# MagnetSensor.net
KiCad netlist of a schematic drawn in Altium Designer
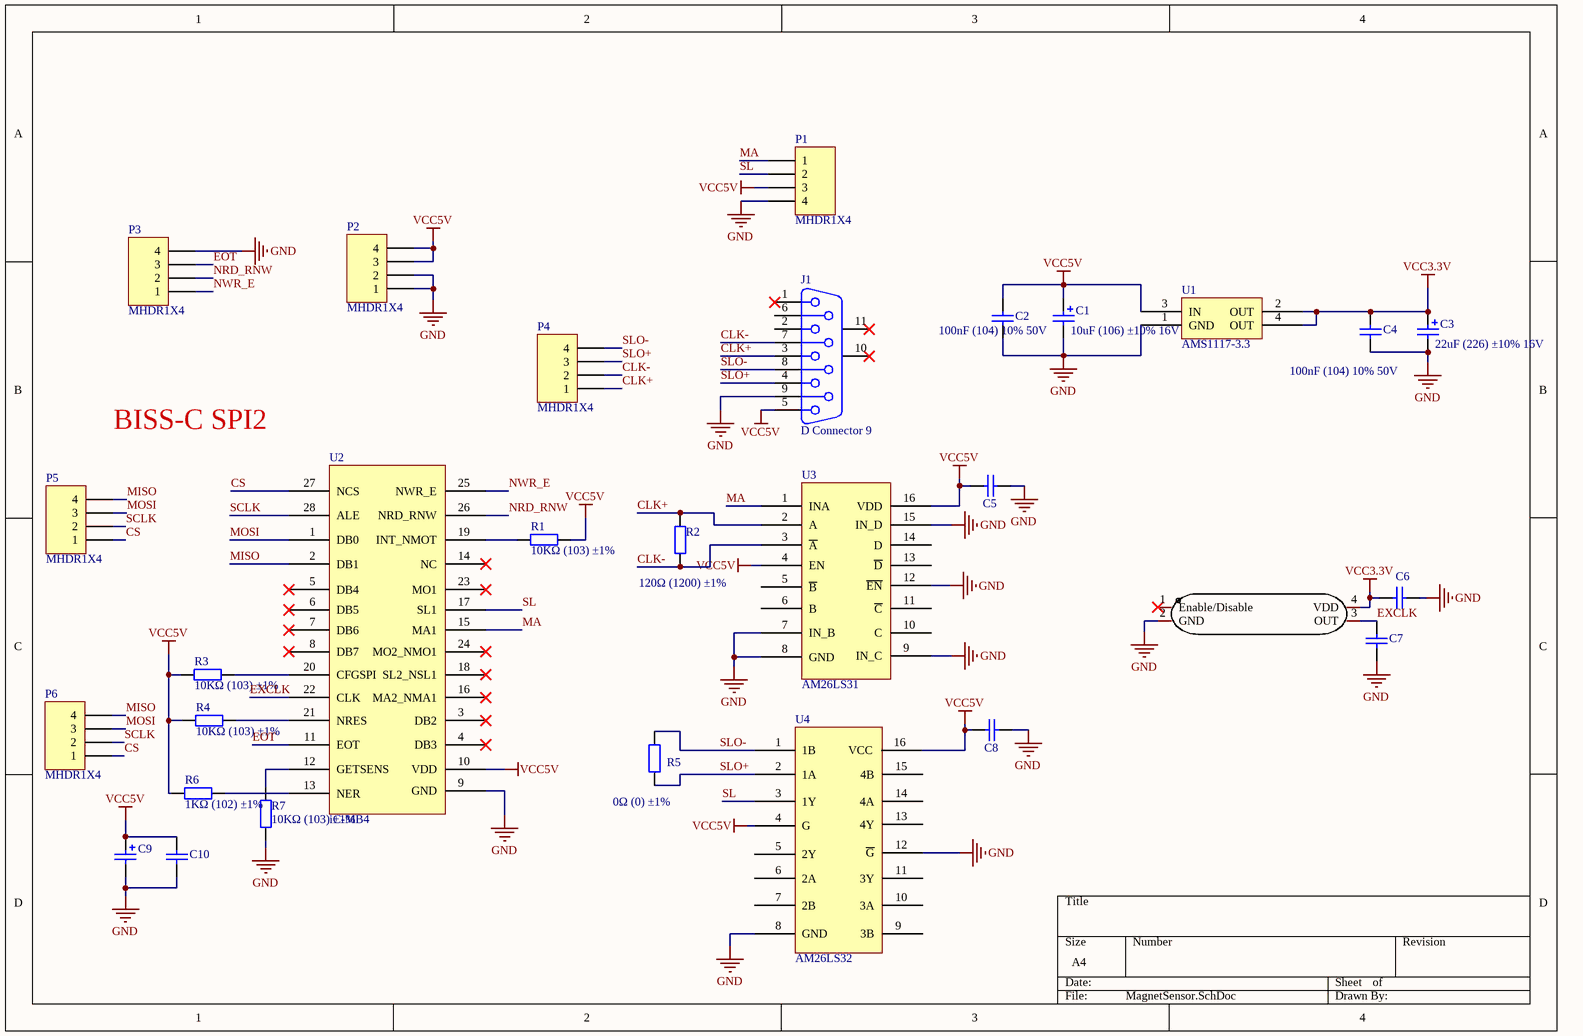
[diagram p0: MagnetSensor.SchDoc]

(export (version "E")
  (design (tool "Eeschema 10.0.6"))
  (components
    (comp (ref "C1")
      (value "10uF (106) ±10% 16V")
      (footprint "CASE-A_3216")
      (description "钽电容")
      (libsource (lib "Cap") (part "3216 10uF (106) 10% 16V"))
    )
    (comp (ref "C2")
      (value "100nF (104) 10% 50V")
      (footprint "0603_C")
      (description "贴片电容")
      (libsource (lib "Cap") (part "0603 100nF (104) 10% 50V"))
    )
    (comp (ref "C3")
      (value "22uF (226) ±10% 16V")
      (footprint "CASE-B_3528")
      (description "钽电容")
      (libsource (lib "Cap") (part "3216 10uF (106) 10% 16V"))
    )
    (comp (ref "C4")
      (value "100nF (104) 10% 50V")
      (footprint "0603_C")
      (description "贴片电容")
      (libsource (lib "Cap") (part "0603 100nF (104) 10% 50V"))
    )
    (comp (ref "C5")
      (value "100nF (104) 10% 50V")
      (footprint "0603_C")
      (description "贴片电容")
      (libsource (lib "Miscellaneous Devices LC") (part "0603 100nF (104) 10% 50V"))
    )
    (comp (ref "C6")
      (value "100nF (104) 10% 50V")
      (footprint "0603_C")
      (description "贴片电容")
      (libsource (lib "Miscellaneous Devices LC") (part "0603 100nF (104) 10% 50V"))
    )
    (comp (ref "C7")
      (value "15uF (104) 10% 50V")
      (footprint "0805_C")
      (description "贴片电容")
      (libsource (lib "Miscellaneous Devices LC") (part "0603 100nF (104) 10% 50V"))
    )
    (comp (ref "C8")
      (value "100nF (104) 10% 50V")
      (footprint "0603_C")
      (description "贴片电容")
      (libsource (lib "Miscellaneous Devices LC") (part "0603 100nF (104) 10% 50V"))
    )
    (comp (ref "C9")
      (value "10uF (106) ±10% 16V")
      (footprint "CASE-A_3216")
      (description "钽电容")
      (libsource (lib "Miscellaneous Devices LC") (part "3216 10uF (106) 10% 16V"))
    )
    (comp (ref "C10")
      (value "100nF (104) 10% 50V")
      (footprint "0603_C")
      (description "贴片电容")
      (libsource (lib "Miscellaneous Devices LC") (part "0603 100nF (104) 10% 50V"))
    )
    (comp (ref "J1")
      (value "D Connector 9")
      (footprint "DSUB1.385-2H9")
      (description "Receptacle Assembly, 9 Position, Right Angle")
      (fields (field (name "PUBLISHER") "Altium Limited"))
      (libsource (lib "Miscellaneous Connectors") (part "D Connector 9"))
    )
    (comp (ref "P1")
      (value "MHDR1X4")
      (footprint "SH1.0-4P-L")
      (description "Header, 4-Pin")
      (fields (field (name "PUBLISHER") "Altium Limited"))
      (libsource (lib "") (part "MHDR1X4_1"))
    )
    (comp (ref "P2")
      (value "MHDR1X4")
      (footprint "SH1.0-4P-L")
      (description "Header, 4-Pin")
      (fields (field (name "PUBLISHER") "Altium Limited"))
      (libsource (lib "Miscellaneous Connectors") (part "MHDR1X4"))
    )
    (comp (ref "P3")
      (value "MHDR1X4")
      (footprint "SH1.0-4P-L")
      (description "Header, 4-Pin")
      (fields (field (name "PUBLISHER") "Altium Limited"))
      (libsource (lib "Miscellaneous Connectors") (part "MHDR1X4"))
    )
    (comp (ref "P4")
      (value "MHDR1X4")
      (footprint "SH1.0-4P-L")
      (description "Header, 4-Pin")
      (fields (field (name "PUBLISHER") "Altium Limited"))
      (libsource (lib "Miscellaneous Connectors") (part "MHDR1X4"))
    )
    (comp (ref "P5")
      (value "MHDR1X4")
      (footprint "SH1.0-4P-L")
      (description "Header, 4-Pin")
      (fields (field (name "PUBLISHER") "Altium Limited"))
      (libsource (lib "Miscellaneous Connectors") (part "MHDR1X4"))
    )
    (comp (ref "P6")
      (value "MHDR1X4")
      (footprint "SH1.0-4P-L")
      (description "Header, 4-Pin")
      (fields (field (name "PUBLISHER") "Altium Limited"))
      (libsource (lib "Miscellaneous Connectors") (part "MHDR1X4"))
    )
    (comp (ref "R1")
      (value "10KΩ (103) ±1%")
      (footprint "0603_R")
      (description "贴片电阻")
      (libsource (lib "") (part "0603 360Ω (3600) 1%_1"))
    )
    (comp (ref "R2")
      (value "120Ω (1200) ±1%")
      (footprint "0603_R")
      (description "贴片电阻")
      (libsource (lib "RES") (part "0603 360Ω (3600) 1%"))
    )
    (comp (ref "R3")
      (value "10KΩ (103) ±1%")
      (footprint "0603_R")
      (description "贴片电阻")
      (libsource (lib "") (part "0603 360Ω (3600) 1%_1"))
    )
    (comp (ref "R4")
      (value "10KΩ (103) ±1%")
      (footprint "0603_R")
      (description "贴片电阻")
      (libsource (lib "") (part "0603 360Ω (3600) 1%_1"))
    )
    (comp (ref "R5")
      (value "0Ω (0) ±1%")
      (footprint "0603_R")
      (description "贴片电阻")
      (libsource (lib "RES") (part "0603 360Ω (3600) 1%"))
    )
    (comp (ref "R6")
      (value "1KΩ (102) ±1%")
      (footprint "0603_R")
      (description "贴片电阻")
      (libsource (lib "") (part "0603 360Ω (3600) 1%_2"))
    )
    (comp (ref "R7")
      (value "10KΩ (103) ±1%")
      (footprint "0603_R")
      (description "贴片电阻")
      (libsource (lib "RES") (part "0603 360Ω (3600) 1%"))
    )
    (comp (ref "U1")
      (value "AMS1117-3.3")
      (footprint "SOT-223")
      (description "3.3V稳压芯片")
      (libsource (lib "Library") (part "AMS1117"))
    )
    (comp (ref "U2")
      (value "iC-MB4")
      (footprint "QFN-28_5x5x05P")
      (description "SPI转BiSS主站芯片")
      (libsource (lib "CAS") (part "iC-MB4"))
    )
    (comp (ref "U3")
      (value "AM26LS31")
      (footprint "SO-16_N")
      (description "AM32LS31 单端转差分芯片")
      (libsource (lib "CAS") (part "AM26LS31"))
    )
    (comp (ref "U4")
      (value "AM26LS32")
      (footprint "SO-16_N")
      (description "AM26LS32 差分转单端")
      (libsource (lib "CAS") (part "AM26LS32"))
    )
    (comp (ref "X1")
      (value "20MHz")
      (footprint "OSC-SMD_4P-L2.5-W2.0-BL")
      (description "2015 osc")
      (fields (field (name "MANUFACTURER") "YXC(扬兴晶振)") (field (name "MANUFACTURER PART") "OT252020MJBA4SL"))
      (libsource (lib "altium-import") (part "root_0_OT252020MJBA4SL_"))
    )
  )
  (nets
    (net (code "1") (name "/CLK+") (class "Default")
      (node (ref "J1") (pin "3") (pinfunction "3_3") (pintype "passive"))
      (node (ref "P4") (pin "1") (pinfunction "1_1") (pintype "passive"))
      (node (ref "R2") (pin "1") (pinfunction "1_1") (pintype "passive"))
      (node (ref "U3") (pin "2") (pinfunction "A_2") (pintype "passive"))
    )
    (net (code "2") (name "/CLK-") (class "Default")
      (node (ref "J1") (pin "7") (pinfunction "7_7") (pintype "passive"))
      (node (ref "P4") (pin "2") (pinfunction "2_2") (pintype "passive"))
      (node (ref "R2") (pin "2") (pinfunction "2_2") (pintype "passive"))
      (node (ref "U3") (pin "3") (pinfunction "~{A}_3") (pintype "passive"))
    )
    (net (code "3") (name "/CS") (class "Default")
      (node (ref "P5") (pin "1") (pinfunction "1_1") (pintype "passive"))
      (node (ref "P6") (pin "1") (pinfunction "1_1") (pintype "passive"))
      (node (ref "U2") (pin "27") (pinfunction "NCS_27") (pintype "passive"))
    )
    (net (code "4") (name "/EOT") (class "Default")
      (node (ref "P3") (pin "3") (pinfunction "3_3") (pintype "passive"))
      (node (ref "U2") (pin "11") (pinfunction "EOT_11") (pintype "passive"))
    )
    (net (code "5") (name "/EXCLK") (class "Default")
      (node (ref "C7") (pin "2") (pinfunction "2_2") (pintype "passive"))
      (node (ref "U2") (pin "22") (pinfunction "CLK_22") (pintype "passive"))
      (node (ref "X1") (pin "3") (pinfunction "OUT_3") (pintype "passive"))
    )
    (net (code "6") (name "/MA") (class "Default")
      (node (ref "P1") (pin "1") (pinfunction "1_1") (pintype "passive"))
      (node (ref "U2") (pin "15") (pinfunction "MA1_15") (pintype "passive"))
      (node (ref "U3") (pin "1") (pinfunction "INA_1") (pintype "passive"))
    )
    (net (code "7") (name "/MISO") (class "Default")
      (node (ref "P5") (pin "4") (pinfunction "4_4") (pintype "passive"))
      (node (ref "P6") (pin "4") (pinfunction "4_4") (pintype "passive"))
      (node (ref "U2") (pin "2") (pinfunction "DB1_2") (pintype "passive"))
    )
    (net (code "8") (name "/MOSI") (class "Default")
      (node (ref "P5") (pin "3") (pinfunction "3_3") (pintype "passive"))
      (node (ref "P6") (pin "3") (pinfunction "3_3") (pintype "passive"))
      (node (ref "U2") (pin "1") (pinfunction "DB0_1") (pintype "passive"))
    )
    (net (code "9") (name "/NRD_RNW") (class "Default")
      (node (ref "P3") (pin "2") (pinfunction "2_2") (pintype "passive"))
      (node (ref "U2") (pin "26") (pinfunction "NRD_RNW_26") (pintype "passive"))
    )
    (net (code "10") (name "/NWR_E") (class "Default")
      (node (ref "P3") (pin "1") (pinfunction "1_1") (pintype "passive"))
      (node (ref "U2") (pin "25") (pinfunction "NWR_E_25") (pintype "passive"))
    )
    (net (code "11") (name "/SCLK") (class "Default")
      (node (ref "P5") (pin "2") (pinfunction "2_2") (pintype "passive"))
      (node (ref "P6") (pin "2") (pinfunction "2_2") (pintype "passive"))
      (node (ref "U2") (pin "28") (pinfunction "ALE_28") (pintype "passive"))
    )
    (net (code "12") (name "/SL") (class "Default")
      (node (ref "P1") (pin "2") (pinfunction "2_2") (pintype "passive"))
      (node (ref "U2") (pin "17") (pinfunction "SL1_17") (pintype "passive"))
      (node (ref "U4") (pin "3") (pinfunction "1Y_3") (pintype "passive"))
    )
    (net (code "13") (name "/SLO+") (class "Default")
      (node (ref "J1") (pin "4") (pinfunction "4_4") (pintype "passive"))
      (node (ref "P4") (pin "3") (pinfunction "3_3") (pintype "passive"))
      (node (ref "R5") (pin "2") (pinfunction "2_2") (pintype "passive"))
      (node (ref "U4") (pin "2") (pinfunction "1A_2") (pintype "passive"))
    )
    (net (code "14") (name "/SLO-") (class "Default")
      (node (ref "J1") (pin "8") (pinfunction "8_8") (pintype "passive"))
      (node (ref "P4") (pin "4") (pinfunction "4_4") (pintype "passive"))
      (node (ref "R5") (pin "1") (pinfunction "1_1") (pintype "passive"))
      (node (ref "U4") (pin "1") (pinfunction "1B_1") (pintype "passive"))
    )
    (net (code "15") (name "GND") (class "Default")
      (node (ref "C1") (pin "2") (pinfunction "2_2") (pintype "passive"))
      (node (ref "C10") (pin "1") (pinfunction "1_1") (pintype "passive"))
      (node (ref "C2") (pin "2") (pinfunction "2_2") (pintype "passive"))
      (node (ref "C3") (pin "2") (pinfunction "2_2") (pintype "passive"))
      (node (ref "C4") (pin "2") (pinfunction "2_2") (pintype "passive"))
      (node (ref "C5") (pin "1") (pinfunction "1_1") (pintype "passive"))
      (node (ref "C6") (pin "1") (pinfunction "1_1") (pintype "passive"))
      (node (ref "C7") (pin "1") (pinfunction "1_1") (pintype "passive"))
      (node (ref "C8") (pin "1") (pinfunction "1_1") (pintype "passive"))
      (node (ref "C9") (pin "2") (pinfunction "2_2") (pintype "passive"))
      (node (ref "J1") (pin "9") (pinfunction "9_9") (pintype "passive"))
      (node (ref "P1") (pin "4") (pinfunction "4_4") (pintype "passive"))
      (node (ref "P2") (pin "1") (pinfunction "1_1") (pintype "passive"))
      (node (ref "P2") (pin "2") (pinfunction "2_2") (pintype "passive"))
      (node (ref "P3") (pin "4") (pinfunction "4_4") (pintype "passive"))
      (node (ref "R7") (pin "2") (pinfunction "2_2") (pintype "passive"))
      (node (ref "U1") (pin "1") (pinfunction "GND_1") (pintype "passive"))
      (node (ref "U2") (pin "9") (pinfunction "GND_9") (pintype "passive"))
      (node (ref "U3") (pin "12") (pinfunction "~{EN}_12") (pintype "passive"))
      (node (ref "U3") (pin "15") (pinfunction "IN_D_15") (pintype "passive"))
      (node (ref "U3") (pin "7") (pinfunction "IN_B_7") (pintype "passive"))
      (node (ref "U3") (pin "8") (pinfunction "GND_8") (pintype "passive"))
      (node (ref "U3") (pin "9") (pinfunction "IN_C_9") (pintype "passive"))
      (node (ref "U4") (pin "12") (pinfunction "~{G}_12") (pintype "passive"))
      (node (ref "U4") (pin "8") (pinfunction "GND_8") (pintype "passive"))
      (node (ref "X1") (pin "2") (pinfunction "GND_2") (pintype "passive"))
    )
    (net (code "16") (name "Net-(U2-CFGSPI)") (class "Default")
      (node (ref "R3") (pin "1") (pinfunction "1_1") (pintype "passive"))
      (node (ref "U2") (pin "20") (pinfunction "CFGSPI_20") (pintype "passive"))
    )
    (net (code "17") (name "Net-(U2-GETSENS)") (class "Default")
      (node (ref "R7") (pin "1") (pinfunction "1_1") (pintype "passive"))
      (node (ref "U2") (pin "12") (pinfunction "GETSENS_12") (pintype "passive"))
    )
    (net (code "18") (name "Net-(U2-INT_NMOT)") (class "Default")
      (node (ref "R1") (pin "2") (pinfunction "2_2") (pintype "passive"))
      (node (ref "U2") (pin "19") (pinfunction "INT_NMOT_19") (pintype "passive"))
    )
    (net (code "19") (name "Net-(U2-NER)") (class "Default")
      (node (ref "R6") (pin "2") (pinfunction "2_2") (pintype "passive"))
      (node (ref "U2") (pin "13") (pinfunction "NER_13") (pintype "passive"))
    )
    (net (code "20") (name "Net-(U2-NRES)") (class "Default")
      (node (ref "R4") (pin "1") (pinfunction "1_1") (pintype "passive"))
      (node (ref "U2") (pin "21") (pinfunction "NRES_21") (pintype "passive"))
    )
    (net (code "21") (name "VCC3.3V") (class "Default")
      (node (ref "C3") (pin "1") (pinfunction "1_1") (pintype "passive"))
      (node (ref "C4") (pin "1") (pinfunction "1_1") (pintype "passive"))
      (node (ref "C6") (pin "2") (pinfunction "2_2") (pintype "passive"))
      (node (ref "U1") (pin "2") (pinfunction "OUT_2") (pintype "passive"))
      (node (ref "U1") (pin "4") (pinfunction "OUT_4") (pintype "passive"))
      (node (ref "X1") (pin "4") (pinfunction "VDD_4") (pintype "passive"))
    )
    (net (code "22") (name "VCC5V") (class "Default")
      (node (ref "C1") (pin "1") (pinfunction "1_1") (pintype "passive"))
      (node (ref "C10") (pin "2") (pinfunction "2_2") (pintype "passive"))
      (node (ref "C2") (pin "1") (pinfunction "1_1") (pintype "passive"))
      (node (ref "C5") (pin "2") (pinfunction "2_2") (pintype "passive"))
      (node (ref "C8") (pin "2") (pinfunction "2_2") (pintype "passive"))
      (node (ref "C9") (pin "1") (pinfunction "1_1") (pintype "passive"))
      (node (ref "J1") (pin "5") (pinfunction "5_5") (pintype "passive"))
      (node (ref "P1") (pin "3") (pinfunction "3_3") (pintype "passive"))
      (node (ref "P2") (pin "3") (pinfunction "3_3") (pintype "passive"))
      (node (ref "P2") (pin "4") (pinfunction "4_4") (pintype "passive"))
      (node (ref "R1") (pin "1") (pinfunction "1_1") (pintype "passive"))
      (node (ref "R3") (pin "2") (pinfunction "2_2") (pintype "passive"))
      (node (ref "R4") (pin "2") (pinfunction "2_2") (pintype "passive"))
      (node (ref "R6") (pin "1") (pinfunction "1_1") (pintype "passive"))
      (node (ref "U1") (pin "3") (pinfunction "IN_3") (pintype "passive"))
      (node (ref "U2") (pin "10") (pinfunction "VDD_10") (pintype "passive"))
      (node (ref "U3") (pin "16") (pinfunction "VDD_16") (pintype "passive"))
      (node (ref "U3") (pin "4") (pinfunction "EN_4") (pintype "passive"))
      (node (ref "U4") (pin "16") (pinfunction "VCC_16") (pintype "passive"))
      (node (ref "U4") (pin "4") (pinfunction "G_4") (pintype "passive"))
    )
    (net (code "23") (name "unconnected-(J1-MH1-Pad10)") (class "Default")
      (node (ref "J1") (pin "10") (pinfunction "MH1_10") (pintype "passive+no_connect"))
    )
    (net (code "24") (name "unconnected-(J1-MH2-Pad11)") (class "Default")
      (node (ref "J1") (pin "11") (pinfunction "MH2_11") (pintype "passive+no_connect"))
    )
    (net (code "25") (name "unconnected-(J1-Pad1)") (class "Default")
      (node (ref "J1") (pin "1") (pinfunction "1_1") (pintype "passive+no_connect"))
    )
    (net (code "26") (name "unconnected-(J1-Pad2)") (class "Default")
      (node (ref "J1") (pin "2") (pinfunction "2_2") (pintype "passive"))
    )
    (net (code "27") (name "unconnected-(J1-Pad6)") (class "Default")
      (node (ref "J1") (pin "6") (pinfunction "6_6") (pintype "passive"))
    )
    (net (code "28") (name "unconnected-(U2-DB2-Pad3)") (class "Default")
      (node (ref "U2") (pin "3") (pinfunction "DB2_3") (pintype "passive+no_connect"))
    )
    (net (code "29") (name "unconnected-(U2-DB3-Pad4)") (class "Default")
      (node (ref "U2") (pin "4") (pinfunction "DB3_4") (pintype "passive+no_connect"))
    )
    (net (code "30") (name "unconnected-(U2-DB4-Pad5)") (class "Default")
      (node (ref "U2") (pin "5") (pinfunction "DB4_5") (pintype "passive+no_connect"))
    )
    (net (code "31") (name "unconnected-(U2-DB5-Pad6)") (class "Default")
      (node (ref "U2") (pin "6") (pinfunction "DB5_6") (pintype "passive+no_connect"))
    )
    (net (code "32") (name "unconnected-(U2-DB6-Pad7)") (class "Default")
      (node (ref "U2") (pin "7") (pinfunction "DB6_7") (pintype "passive+no_connect"))
    )
    (net (code "33") (name "unconnected-(U2-DB7-Pad8)") (class "Default")
      (node (ref "U2") (pin "8") (pinfunction "DB7_8") (pintype "passive+no_connect"))
    )
    (net (code "34") (name "unconnected-(U2-MA2_NMA1-Pad16)") (class "Default")
      (node (ref "U2") (pin "16") (pinfunction "MA2_NMA1_16") (pintype "passive+no_connect"))
    )
    (net (code "35") (name "unconnected-(U2-MO1-Pad23)") (class "Default")
      (node (ref "U2") (pin "23") (pinfunction "MO1_23") (pintype "passive+no_connect"))
    )
    (net (code "36") (name "unconnected-(U2-MO2_NMO1-Pad24)") (class "Default")
      (node (ref "U2") (pin "24") (pinfunction "MO2_NMO1_24") (pintype "passive+no_connect"))
    )
    (net (code "37") (name "unconnected-(U2-NC-Pad14)") (class "Default")
      (node (ref "U2") (pin "14") (pinfunction "NC_14") (pintype "passive+no_connect"))
    )
    (net (code "38") (name "unconnected-(U2-SL2_NSL1-Pad18)") (class "Default")
      (node (ref "U2") (pin "18") (pinfunction "SL2_NSL1_18") (pintype "passive+no_connect"))
    )
    (net (code "39") (name "unconnected-(U3-B-Pad6)") (class "Default")
      (node (ref "U3") (pin "6") (pinfunction "B_6") (pintype "passive"))
    )
    (net (code "40") (name "unconnected-(U3-C-Pad10)") (class "Default")
      (node (ref "U3") (pin "10") (pinfunction "C_10") (pintype "passive"))
    )
    (net (code "41") (name "unconnected-(U3-D-Pad14)") (class "Default")
      (node (ref "U3") (pin "14") (pinfunction "D_14") (pintype "passive"))
    )
    (net (code "42") (name "unconnected-(U3-~{B}-Pad5)") (class "Default")
      (node (ref "U3") (pin "5") (pinfunction "~{B}_5") (pintype "passive"))
    )
    (net (code "43") (name "unconnected-(U3-~{C}-Pad11)") (class "Default")
      (node (ref "U3") (pin "11") (pinfunction "~{C}_11") (pintype "passive"))
    )
    (net (code "44") (name "unconnected-(U3-~{D}-Pad13)") (class "Default")
      (node (ref "U3") (pin "13") (pinfunction "~{D}_13") (pintype "passive"))
    )
    (net (code "45") (name "unconnected-(U4-2A-Pad6)") (class "Default")
      (node (ref "U4") (pin "6") (pinfunction "2A_6") (pintype "passive"))
    )
    (net (code "46") (name "unconnected-(U4-2B-Pad7)") (class "Default")
      (node (ref "U4") (pin "7") (pinfunction "2B_7") (pintype "passive"))
    )
    (net (code "47") (name "unconnected-(U4-2Y-Pad5)") (class "Default")
      (node (ref "U4") (pin "5") (pinfunction "2Y_5") (pintype "passive"))
    )
    (net (code "48") (name "unconnected-(U4-3A-Pad10)") (class "Default")
      (node (ref "U4") (pin "10") (pinfunction "3A_10") (pintype "passive"))
    )
    (net (code "49") (name "unconnected-(U4-3B-Pad9)") (class "Default")
      (node (ref "U4") (pin "9") (pinfunction "3B_9") (pintype "passive"))
    )
    (net (code "50") (name "unconnected-(U4-3Y-Pad11)") (class "Default")
      (node (ref "U4") (pin "11") (pinfunction "3Y_11") (pintype "passive"))
    )
    (net (code "51") (name "unconnected-(U4-4A-Pad14)") (class "Default")
      (node (ref "U4") (pin "14") (pinfunction "4A_14") (pintype "passive"))
    )
    (net (code "52") (name "unconnected-(U4-4B-Pad15)") (class "Default")
      (node (ref "U4") (pin "15") (pinfunction "4B_15") (pintype "passive"))
    )
    (net (code "53") (name "unconnected-(U4-4Y-Pad13)") (class "Default")
      (node (ref "U4") (pin "13") (pinfunction "4Y_13") (pintype "passive"))
    )
    (net (code "54") (name "unconnected-(X1-Enable{slash}Disable-Pad1)") (class "Default")
      (node (ref "X1") (pin "1") (pinfunction "Enable/Disable_1") (pintype "passive+no_connect"))
    )
  )
)
